# Wapuugotchi.net
KiCad netlist of a schematic drawn in EAGLE
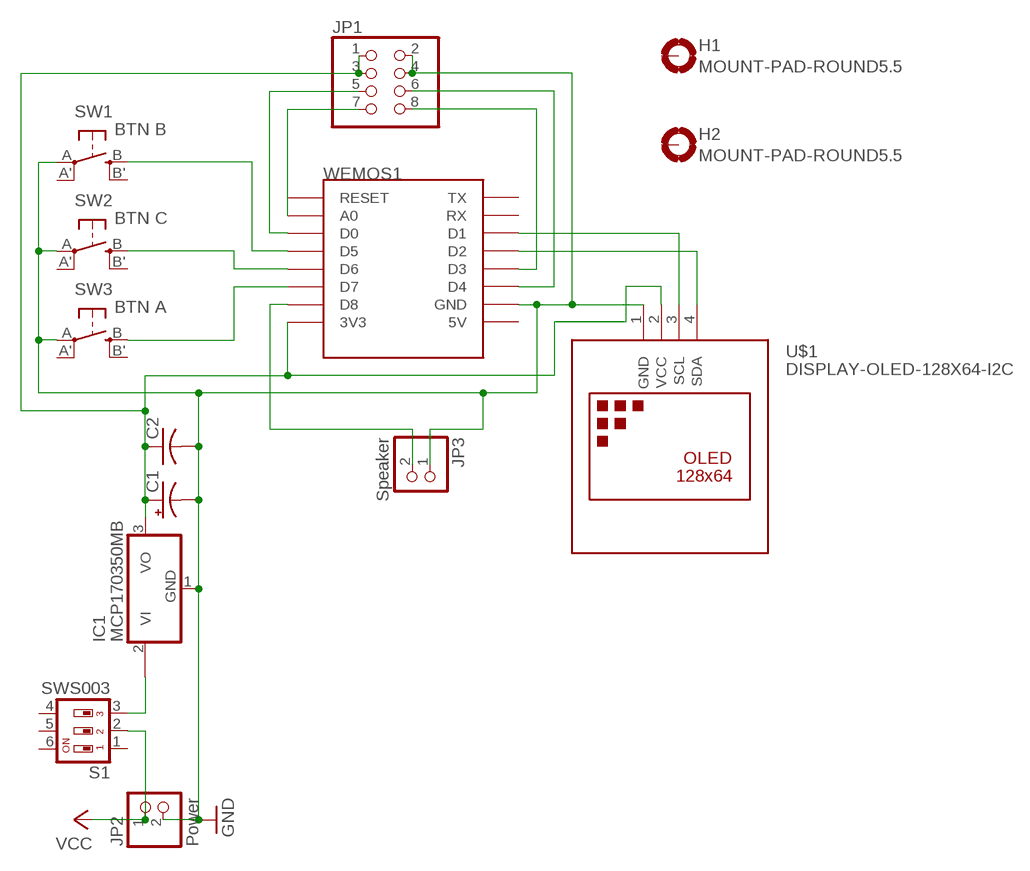
[diagram p0: schematic, sheet 1]

(export (version "E")
  (design (tool "Eeschema 10.0.6"))
  (components
    (comp (ref "C1")
      (value "CPOL-US153CLV-1012")
      (footprint "eagle-import:153CLV-1012")
      (libsource (lib "eagle-import") (part "CPOL-US153CLV-1012"))
    )
    (comp (ref "C2")
      (value "C-USC0805")
      (footprint "eagle-import:C0805")
      (libsource (lib "eagle-import") (part "C-USC0805"))
    )
    (comp (ref "H1")
      (value "MOUNT-PAD-ROUND5.5")
      (footprint "eagle-import:5,5-PAD")
      (libsource (lib "eagle-import") (part "MOUNT-PAD-ROUND5.5"))
    )
    (comp (ref "H2")
      (value "MOUNT-PAD-ROUND5.5")
      (footprint "eagle-import:5,5-PAD")
      (libsource (lib "eagle-import") (part "MOUNT-PAD-ROUND5.5"))
    )
    (comp (ref "IC1")
      (value "MCP170350MB")
      (footprint "eagle-import:SOT89")
      (libsource (lib "eagle-import") (part "MCP1703MB50"))
    )
    (comp (ref "JP1")
      (value "PINHD-2X4")
      (footprint "eagle-import:2X04")
      (libsource (lib "eagle-import") (part "PINHD-2X4"))
    )
    (comp (ref "JP2")
      (value "Power")
      (footprint "eagle-import:1X02")
      (libsource (lib "eagle-import") (part "PINHD-1X2"))
    )
    (comp (ref "JP3")
      (value "Speaker")
      (footprint "eagle-import:1X02")
      (libsource (lib "eagle-import") (part "PINHD-1X2"))
    )
    (comp (ref "S1")
      (value "SWS003")
      (footprint "eagle-import:SMS-003")
      (libsource (lib "eagle-import") (part "SWS003"))
    )
    (comp (ref "SW1")
      (value "BTN B")
      (footprint "eagle-import:EVQ-Q2")
      (libsource (lib "eagle-import") (part "SPST_TACT-EVQQ2"))
    )
    (comp (ref "SW2")
      (value "BTN C")
      (footprint "eagle-import:EVQ-Q2")
      (libsource (lib "eagle-import") (part "SPST_TACT-EVQQ2"))
    )
    (comp (ref "SW3")
      (value "BTN A")
      (footprint "eagle-import:EVQ-Q2")
      (libsource (lib "eagle-import") (part "SPST_TACT-EVQQ2"))
    )
    (comp (ref "U$1")
      (value "DISPLAY-OLED-128X64-I2C")
      (footprint "eagle-import:DISPLAY-OLED-128X64-I2C")
      (libsource (lib "eagle-import") (part "DISPLAY-OLED-128X64-I2C"))
    )
    (comp (ref "WEMOS1")
      (value "WEMOS-D1-MINI")
      (footprint "eagle-import:WEMOS-D1-MINI")
      (libsource (lib "eagle-import") (part "WEMOS-D1-MINI"))
    )
  )
  (nets
    (net (code "1") (name "GND") (class "Default")
      (node (ref "C1") (pin "-") (pinfunction "-_-") (pintype "passive"))
      (node (ref "C2") (pin "2") (pinfunction "2_2") (pintype "passive"))
      (node (ref "IC1") (pin "1") (pinfunction "GND_1") (pintype "passive"))
      (node (ref "JP1") (pin "2") (pinfunction "2_2") (pintype "passive"))
      (node (ref "JP1") (pin "4") (pinfunction "4_4") (pintype "passive"))
      (node (ref "JP2") (pin "2") (pinfunction "2_2") (pintype "passive"))
      (node (ref "JP3") (pin "1") (pinfunction "1_1") (pintype "passive"))
      (node (ref "SW1") (pin "A") (pinfunction "P_A") (pintype "passive"))
      (node (ref "SW2") (pin "A") (pinfunction "P_A") (pintype "passive"))
      (node (ref "SW3") (pin "A") (pinfunction "P_A") (pintype "passive"))
      (node (ref "U$1") (pin "1") (pinfunction "GND_1") (pintype "power_in"))
      (node (ref "WEMOS1") (pin "GND") (pinfunction "GND_GND") (pintype "bidirectional"))
    )
    (net (code "2") (name "Net-(IC1-VI1)") (class "Default")
      (node (ref "IC1") (pin "2@1") (pinfunction "VI1_2@1") (pintype "input"))
      (node (ref "S1") (pin "3") (pinfunction "3_3") (pintype "passive"))
    )
    (net (code "3") (name "Net-(IC1-VO)") (class "Default")
      (node (ref "C1") (pin "+") (pinfunction "+_+") (pintype "passive"))
      (node (ref "C2") (pin "1") (pinfunction "1_1") (pintype "passive"))
      (node (ref "IC1") (pin "3") (pinfunction "VO_3") (pintype "passive"))
      (node (ref "JP1") (pin "1") (pinfunction "1_1") (pintype "passive"))
      (node (ref "JP1") (pin "3") (pinfunction "3_3") (pintype "passive"))
      (node (ref "U$1") (pin "2") (pinfunction "VCC_2") (pintype "power_in"))
      (node (ref "WEMOS1") (pin "3V3") (pinfunction "3V3_3V3") (pintype "bidirectional"))
    )
    (net (code "4") (name "Net-(JP1-Pad5)") (class "Default")
      (node (ref "JP1") (pin "5") (pinfunction "5_5") (pintype "passive"))
      (node (ref "WEMOS1") (pin "D0") (pinfunction "D0_D0") (pintype "bidirectional"))
    )
    (net (code "5") (name "Net-(JP1-Pad6)") (class "Default")
      (node (ref "JP1") (pin "6") (pinfunction "6_6") (pintype "passive"))
      (node (ref "WEMOS1") (pin "D4") (pinfunction "D4_D4") (pintype "bidirectional"))
    )
    (net (code "6") (name "Net-(JP1-Pad7)") (class "Default")
      (node (ref "JP1") (pin "7") (pinfunction "7_7") (pintype "passive"))
      (node (ref "WEMOS1") (pin "A0") (pinfunction "A0_A0") (pintype "bidirectional"))
    )
    (net (code "7") (name "Net-(JP1-Pad8)") (class "Default")
      (node (ref "JP1") (pin "8") (pinfunction "8_8") (pintype "passive"))
      (node (ref "WEMOS1") (pin "D3") (pinfunction "D3_D3") (pintype "bidirectional"))
    )
    (net (code "8") (name "Net-(JP3-Pad2)") (class "Default")
      (node (ref "JP3") (pin "2") (pinfunction "2_2") (pintype "passive"))
      (node (ref "WEMOS1") (pin "D8") (pinfunction "D8_D8") (pintype "bidirectional"))
    )
    (net (code "9") (name "Net-(SW1-S)") (class "Default")
      (node (ref "SW1") (pin "B") (pinfunction "S_B") (pintype "passive"))
      (node (ref "WEMOS1") (pin "D5") (pinfunction "D5_D5") (pintype "bidirectional"))
    )
    (net (code "10") (name "Net-(SW2-S)") (class "Default")
      (node (ref "SW2") (pin "B") (pinfunction "S_B") (pintype "passive"))
      (node (ref "WEMOS1") (pin "D6") (pinfunction "D6_D6") (pintype "bidirectional"))
    )
    (net (code "11") (name "Net-(SW3-S)") (class "Default")
      (node (ref "SW3") (pin "B") (pinfunction "S_B") (pintype "passive"))
      (node (ref "WEMOS1") (pin "D7") (pinfunction "D7_D7") (pintype "bidirectional"))
    )
    (net (code "12") (name "Net-(U$1-SCL)") (class "Default")
      (node (ref "U$1") (pin "3") (pinfunction "SCL_3") (pintype "bidirectional"))
      (node (ref "WEMOS1") (pin "D1") (pinfunction "D1_D1") (pintype "bidirectional"))
    )
    (net (code "13") (name "Net-(U$1-SDA)") (class "Default")
      (node (ref "U$1") (pin "4") (pinfunction "SDA_4") (pintype "bidirectional"))
      (node (ref "WEMOS1") (pin "D2") (pinfunction "D2_D2") (pintype "bidirectional"))
    )
    (net (code "14") (name "VCC") (class "Default")
      (node (ref "JP2") (pin "1") (pinfunction "1_1") (pintype "passive"))
      (node (ref "S1") (pin "2") (pinfunction "2_2") (pintype "passive"))
    )
    (net (code "15") (name "unconnected-(H1-MOUNT-PadB5,5)") (class "Default")
      (node (ref "H1") (pin "B5,5") (pinfunction "MOUNT_B5,5") (pintype "passive"))
    )
    (net (code "16") (name "unconnected-(H2-MOUNT-PadB5,5)") (class "Default")
      (node (ref "H2") (pin "B5,5") (pinfunction "MOUNT_B5,5") (pintype "passive"))
    )
    (net (code "17") (name "unconnected-(IC1-VI-Pad2)") (class "Default")
      (node (ref "IC1") (pin "2") (pinfunction "VI_2") (pintype "input"))
    )
    (net (code "18") (name "unconnected-(S1-Pad1)") (class "Default")
      (node (ref "S1") (pin "1") (pinfunction "1_1") (pintype "passive"))
    )
    (net (code "19") (name "unconnected-(S1-Pad4)") (class "Default")
      (node (ref "S1") (pin "4") (pinfunction "4_4") (pintype "passive"))
    )
    (net (code "20") (name "unconnected-(S1-Pad5)") (class "Default")
      (node (ref "S1") (pin "5") (pinfunction "5_5") (pintype "passive"))
    )
    (net (code "21") (name "unconnected-(S1-Pad6)") (class "Default")
      (node (ref "S1") (pin "6") (pinfunction "6_6") (pintype "passive"))
    )
    (net (code "22") (name "unconnected-(SW1-P1-PadA')") (class "Default")
      (node (ref "SW1") (pin "A'") (pinfunction "P1_A'") (pintype "passive"))
    )
    (net (code "23") (name "unconnected-(SW1-S1-PadB')") (class "Default")
      (node (ref "SW1") (pin "B'") (pinfunction "S1_B'") (pintype "passive"))
    )
    (net (code "24") (name "unconnected-(SW2-P1-PadA')") (class "Default")
      (node (ref "SW2") (pin "A'") (pinfunction "P1_A'") (pintype "passive"))
    )
    (net (code "25") (name "unconnected-(SW2-S1-PadB')") (class "Default")
      (node (ref "SW2") (pin "B'") (pinfunction "S1_B'") (pintype "passive"))
    )
    (net (code "26") (name "unconnected-(SW3-P1-PadA')") (class "Default")
      (node (ref "SW3") (pin "A'") (pinfunction "P1_A'") (pintype "passive"))
    )
    (net (code "27") (name "unconnected-(SW3-S1-PadB')") (class "Default")
      (node (ref "SW3") (pin "B'") (pinfunction "S1_B'") (pintype "passive"))
    )
    (net (code "28") (name "unconnected-(WEMOS1-Pad5V)") (class "Default")
      (node (ref "WEMOS1") (pin "5V") (pinfunction "5V_5V") (pintype "bidirectional"))
    )
    (net (code "29") (name "unconnected-(WEMOS1-PadRESET)") (class "Default")
      (node (ref "WEMOS1") (pin "RESET") (pinfunction "RESET_RESET") (pintype "bidirectional"))
    )
    (net (code "30") (name "unconnected-(WEMOS1-PadRX)") (class "Default")
      (node (ref "WEMOS1") (pin "RX") (pinfunction "RX_RX") (pintype "bidirectional"))
    )
    (net (code "31") (name "unconnected-(WEMOS1-PadTX)") (class "Default")
      (node (ref "WEMOS1") (pin "TX") (pinfunction "TX_TX") (pintype "bidirectional"))
    )
  )
)
